# 01_MAIN.net
KiCad netlist of a schematic drawn in Altium Designer
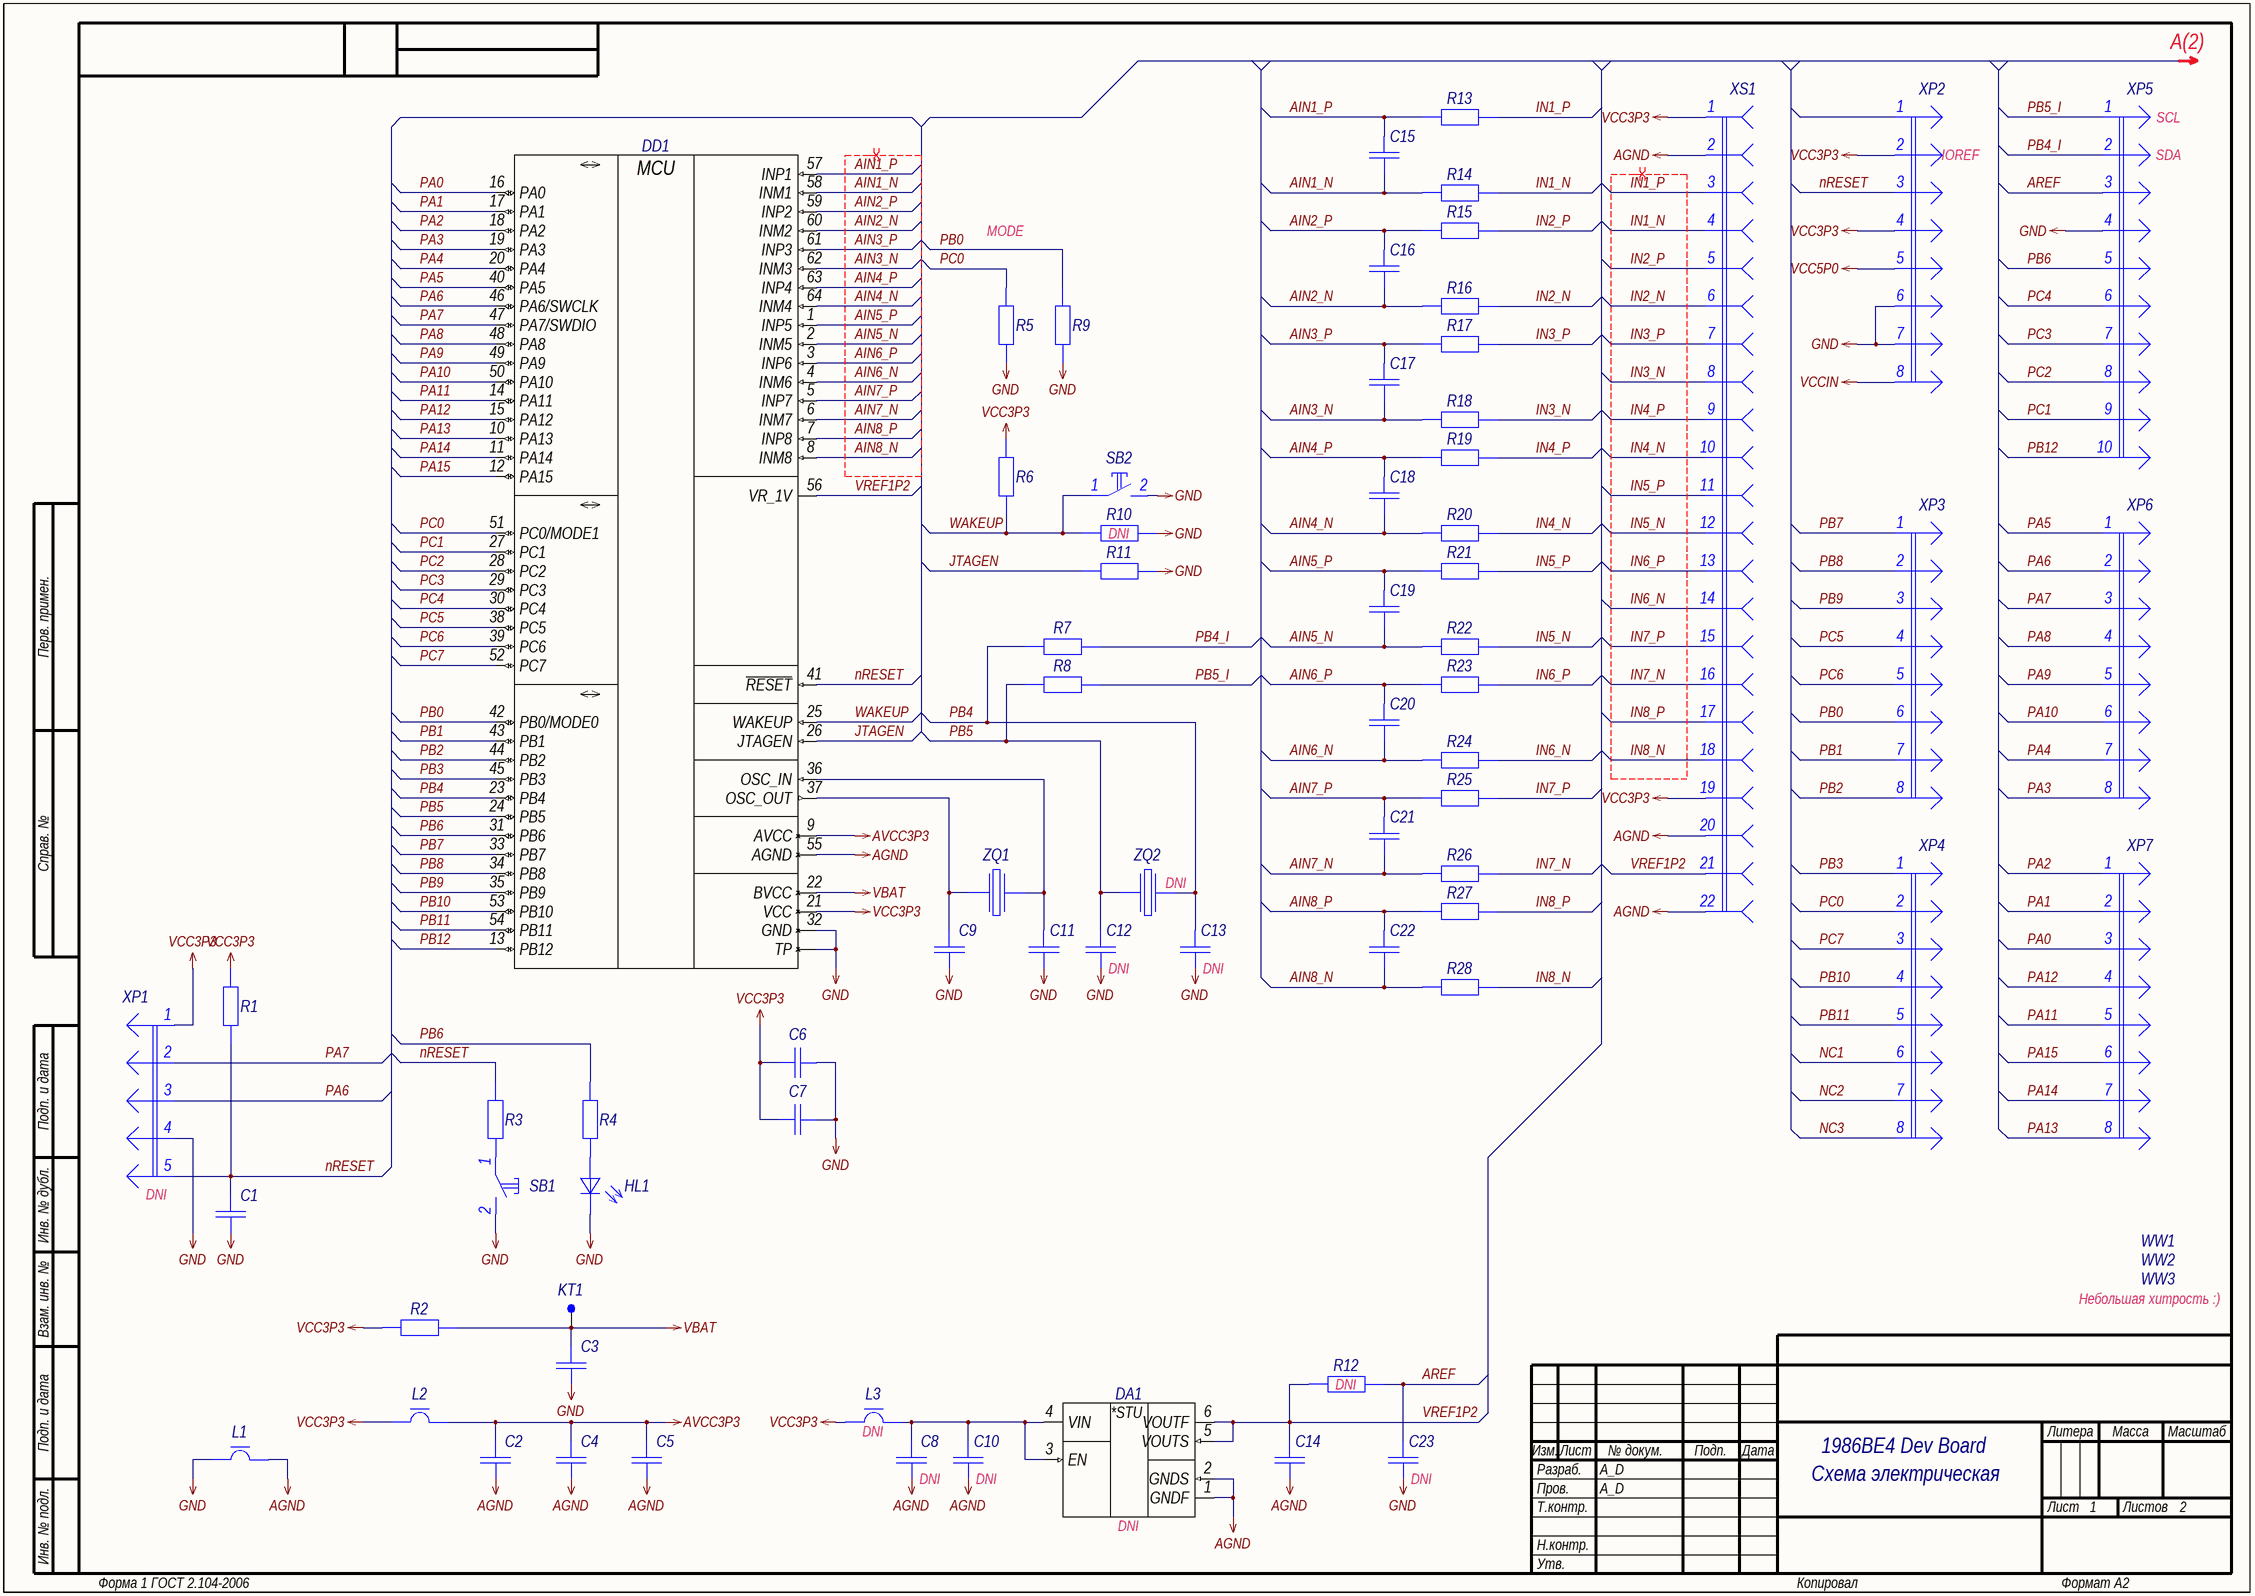
[diagram p0: 01_MAIN.SchDoc]

(export (version "E")
  (design (tool "Eeschema 10.0.6"))
  (components
    (comp (ref "C1")
      (value "Capacitor")
      (footprint "C0603_L")
      (fields
        (field (name "PART NUMBER") "GRM188R72A104KA35D")
        (field (name "VOLTAGE") "100V")
        (field (name "TOLERANCE") "±10%")
        (field (name "PUBLISHER") "Andrew Danich")
      )
      (libsource (lib "ADLib") (part "Capacitor"))
    )
    (comp (ref "C2")
      (value "Capacitor")
      (footprint "C0603_L")
      (fields
        (field (name "PART NUMBER") "GRM188R60J106ME47D")
        (field (name "VOLTAGE") "6.3V")
        (field (name "TOLERANCE") "±20%")
        (field (name "PUBLISHER") "Andrew Danich")
      )
      (libsource (lib "ADLib") (part "Capacitor"))
    )
    (comp (ref "C3")
      (value "Capacitor")
      (footprint "C0603_L")
      (fields
        (field (name "PART NUMBER") "GRM188R72A104KA35D")
        (field (name "VOLTAGE") "100V")
        (field (name "TOLERANCE") "±10%")
        (field (name "PUBLISHER") "Andrew Danich")
      )
      (libsource (lib "ADLib") (part "Capacitor"))
    )
    (comp (ref "C4")
      (value "Capacitor")
      (footprint "C0603_L")
      (fields
        (field (name "PART NUMBER") "GRM188R72A104KA35D")
        (field (name "VOLTAGE") "100V")
        (field (name "TOLERANCE") "±10%")
        (field (name "PUBLISHER") "Andrew Danich")
      )
      (libsource (lib "ADLib") (part "Capacitor"))
    )
    (comp (ref "C5")
      (value "Capacitor")
      (footprint "C0603_L")
      (fields
        (field (name "PART NUMBER") "GCJ188R72A103KA01D")
        (field (name "VOLTAGE") "100V")
        (field (name "TOLERANCE") "±10%")
        (field (name "PUBLISHER") "Andrew Danich")
      )
      (libsource (lib "ADLib") (part "Capacitor"))
    )
    (comp (ref "C6")
      (value "Capacitor")
      (footprint "C0603_L")
      (fields
        (field (name "PART NUMBER") "GRM188R72A104KA35D")
        (field (name "VOLTAGE") "100V")
        (field (name "TOLERANCE") "±10%")
        (field (name "PUBLISHER") "Andrew Danich")
      )
      (libsource (lib "ADLib") (part "Capacitor"))
    )
    (comp (ref "C7")
      (value "Capacitor")
      (footprint "C0603_L")
      (fields
        (field (name "PART NUMBER") "GCM188R71E105KA64D")
        (field (name "VOLTAGE") "25V")
        (field (name "TOLERANCE") "±10%")
        (field (name "PUBLISHER") "Andrew Danich")
      )
      (libsource (lib "ADLib") (part "Capacitor"))
    )
    (comp (ref "C8")
      (value "Capacitor")
      (footprint "C0603_L")
      (fields
        (field (name "PART NUMBER") "GCM188R71E105KA64D")
        (field (name "VOLTAGE") "25V")
        (field (name "TOLERANCE") "±10%")
        (field (name "PUBLISHER") "Andrew Danich")
      )
      (libsource (lib "ADLib") (part "Capacitor"))
    )
    (comp (ref "C9")
      (value "Capacitor")
      (footprint "C0603_L")
      (fields
        (field (name "PART NUMBER") "GCM1885C1H150JA16D")
        (field (name "VOLTAGE") "50V")
        (field (name "TOLERANCE") "±5%")
        (field (name "PUBLISHER") "Andrew Danich")
      )
      (libsource (lib "ADLib") (part "Capacitor"))
    )
    (comp (ref "C10")
      (value "Capacitor")
      (footprint "C0603_L")
      (fields
        (field (name "PART NUMBER") "GRM188R72A104KA35D")
        (field (name "VOLTAGE") "100V")
        (field (name "TOLERANCE") "±10%")
        (field (name "PUBLISHER") "Andrew Danich")
      )
      (libsource (lib "ADLib") (part "Capacitor"))
    )
    (comp (ref "C11")
      (value "Capacitor")
      (footprint "C0603_L")
      (fields
        (field (name "PART NUMBER") "GCM1885C1H150JA16D")
        (field (name "VOLTAGE") "50V")
        (field (name "TOLERANCE") "±5%")
        (field (name "PUBLISHER") "Andrew Danich")
      )
      (libsource (lib "ADLib") (part "Capacitor"))
    )
    (comp (ref "C12")
      (value "Capacitor")
      (footprint "C0603_L")
      (fields
        (field (name "PART NUMBER") "GCM1885C2A120JA16D")
        (field (name "VOLTAGE") "100V")
        (field (name "TOLERANCE") "±5%")
        (field (name "PUBLISHER") "Andrew Danich")
      )
      (libsource (lib "ADLib") (part "Capacitor"))
    )
    (comp (ref "C13")
      (value "Capacitor")
      (footprint "C0603_L")
      (fields
        (field (name "PART NUMBER") "GCM1885C2A120JA16D")
        (field (name "VOLTAGE") "100V")
        (field (name "TOLERANCE") "±5%")
        (field (name "PUBLISHER") "Andrew Danich")
      )
      (libsource (lib "ADLib") (part "Capacitor"))
    )
    (comp (ref "C14")
      (value "Capacitor")
      (footprint "C0603_L")
      (fields
        (field (name "PART NUMBER") "GRM188R72A104KA35D")
        (field (name "VOLTAGE") "100V")
        (field (name "TOLERANCE") "±10%")
        (field (name "PUBLISHER") "Andrew Danich")
      )
      (libsource (lib "ADLib") (part "Capacitor"))
    )
    (comp (ref "C15")
      (value "Capacitor")
      (footprint "C0603_L")
      (fields
        (field (name "PART NUMBER") "GCM1885C2A101JA16D")
        (field (name "VOLTAGE") "100V")
        (field (name "TOLERANCE") "±5%")
        (field (name "PUBLISHER") "Andrew Danich")
      )
      (libsource (lib "ADLib") (part "Capacitor"))
    )
    (comp (ref "C16")
      (value "Capacitor")
      (footprint "C0603_L")
      (fields
        (field (name "PART NUMBER") "GCM1885C2A101JA16D")
        (field (name "VOLTAGE") "100V")
        (field (name "TOLERANCE") "±5%")
        (field (name "PUBLISHER") "Andrew Danich")
      )
      (libsource (lib "ADLib") (part "Capacitor"))
    )
    (comp (ref "C17")
      (value "Capacitor")
      (footprint "C0603_L")
      (fields
        (field (name "PART NUMBER") "GCM1885C2A101JA16D")
        (field (name "VOLTAGE") "100V")
        (field (name "TOLERANCE") "±5%")
        (field (name "PUBLISHER") "Andrew Danich")
      )
      (libsource (lib "ADLib") (part "Capacitor"))
    )
    (comp (ref "C18")
      (value "Capacitor")
      (footprint "C0603_L")
      (fields
        (field (name "PART NUMBER") "GCM1885C2A101JA16D")
        (field (name "VOLTAGE") "100V")
        (field (name "TOLERANCE") "±5%")
        (field (name "PUBLISHER") "Andrew Danich")
      )
      (libsource (lib "ADLib") (part "Capacitor"))
    )
    (comp (ref "C19")
      (value "Capacitor")
      (footprint "C0603_L")
      (fields
        (field (name "PART NUMBER") "GCM1885C2A101JA16D")
        (field (name "VOLTAGE") "100V")
        (field (name "TOLERANCE") "±5%")
        (field (name "PUBLISHER") "Andrew Danich")
      )
      (libsource (lib "ADLib") (part "Capacitor"))
    )
    (comp (ref "C20")
      (value "Capacitor")
      (footprint "C0603_L")
      (fields
        (field (name "PART NUMBER") "GCM1885C2A101JA16D")
        (field (name "VOLTAGE") "100V")
        (field (name "TOLERANCE") "±5%")
        (field (name "PUBLISHER") "Andrew Danich")
      )
      (libsource (lib "ADLib") (part "Capacitor"))
    )
    (comp (ref "C21")
      (value "Capacitor")
      (footprint "C0603_L")
      (fields
        (field (name "PART NUMBER") "GCM1885C2A101JA16D")
        (field (name "VOLTAGE") "100V")
        (field (name "TOLERANCE") "±5%")
        (field (name "PUBLISHER") "Andrew Danich")
      )
      (libsource (lib "ADLib") (part "Capacitor"))
    )
    (comp (ref "C22")
      (value "Capacitor")
      (footprint "C0603_L")
      (fields
        (field (name "PART NUMBER") "GCM1885C2A101JA16D")
        (field (name "VOLTAGE") "100V")
        (field (name "TOLERANCE") "±5%")
        (field (name "PUBLISHER") "Andrew Danich")
      )
      (libsource (lib "ADLib") (part "Capacitor"))
    )
    (comp (ref "C23")
      (value "Capacitor")
      (footprint "C0603_L")
      (fields
        (field (name "PART NUMBER") "GRM188R72A104KA35D")
        (field (name "VOLTAGE") "100V")
        (field (name "TOLERANCE") "±10%")
        (field (name "PUBLISHER") "Andrew Danich")
      )
      (libsource (lib "ADLib") (part "Capacitor"))
    )
    (comp (ref "DA1")
      (value "ADR34xx-Series")
      (footprint "TSOT-23-6_095P290X160X100_N")
      (fields
        (field (name "PART NUMBER") "ADR3412ARJZ-R7")
        (field (name "MANUFACTURER") "Analog Devices")
        (field (name "PUBLISHER") "Andrew Danich")
      )
      (libsource (lib "ADLib") (part "ADR34xx-Series"))
    )
    (comp (ref "DD1")
      (value "1986ВЕ4У1-Series")
      (footprint "5153.64-1")
      (fields
        (field (name "PART NUMBER") "К1986ВЕ4У1К")
        (field (name "MANUFACTURER") "Миландр")
        (field (name "PUBLISHER") "Andrew Danich")
      )
      (libsource (lib "ADLib_RUS") (part "1986ВЕ4У1-Series"))
    )
    (comp (ref "HL1")
      (value "TEST")
      (footprint "LD0603_L")
      (fields (field (name "PART NUMBER") "BL-LS0603DNB") (field (name "PUBLISHER") "Andrew Danich"))
      (libsource (lib "ADLib") (part "Led-1"))
    )
    (comp (ref "KT1")
      (value "VBAT")
      (footprint "TP-SMT-C-0.8mm")
      (fields (field (name "PART NUMBER") "TestPoint-SMT") (field (name "PUBLISHER") "Andrew Danich"))
      (libsource (lib "ADLib") (part "TP-S-1"))
    )
    (comp (ref "L1")
      (value "FerriteBead")
      (footprint "L0805_L")
      (fields
        (field (name "PART NUMBER") "BLM21PG331SN1")
        (field (name "TOLERANCE") "±25%")
        (field (name "MANUFACTURER") "Murata")
        (field (name "PUBLISHER") "Andrew Danich")
      )
      (libsource (lib "ADLib") (part "FerriteBead"))
    )
    (comp (ref "L2")
      (value "FerriteBead")
      (footprint "L0603_L")
      (fields
        (field (name "PART NUMBER") "BLM18PG331SN1")
        (field (name "TOLERANCE") "±25%")
        (field (name "MANUFACTURER") "Murata")
        (field (name "PUBLISHER") "Andrew Danich")
      )
      (libsource (lib "ADLib") (part "FerriteBead"))
    )
    (comp (ref "L3")
      (value "FerriteBead")
      (footprint "L0603_L")
      (fields
        (field (name "PART NUMBER") "BLM18PG331SN1")
        (field (name "TOLERANCE") "±25%")
        (field (name "MANUFACTURER") "Murata")
        (field (name "PUBLISHER") "Andrew Danich")
      )
      (libsource (lib "ADLib") (part "FerriteBead"))
    )
    (comp (ref "R1")
      (value "Resistor")
      (footprint "R0603_L")
      (fields
        (field (name "PART NUMBER") "RC0603JR-0710KL")
        (field (name "TOLERANCE") "±5%")
        (field (name "MANUFACTURER") "Yageo")
        (field (name "PUBLISHER") "Andrew Danich")
      )
      (libsource (lib "ADLib") (part "Resistor"))
    )
    (comp (ref "R2")
      (value "Resistor")
      (footprint "R0603_L")
      (fields
        (field (name "PART NUMBER") "RC0603JR-070R")
        (field (name "TOLERANCE") "±5%")
        (field (name "MANUFACTURER") "Yageo")
        (field (name "PUBLISHER") "Andrew Danich")
      )
      (libsource (lib "ADLib") (part "Resistor"))
    )
    (comp (ref "R3")
      (value "Resistor")
      (footprint "R0603_L")
      (fields
        (field (name "PART NUMBER") "RC0603JR-07100R")
        (field (name "TOLERANCE") "±5%")
        (field (name "MANUFACTURER") "Yageo")
        (field (name "PUBLISHER") "Andrew Danich")
      )
      (libsource (lib "ADLib") (part "Resistor"))
    )
    (comp (ref "R4")
      (value "Resistor")
      (footprint "R0603_L")
      (fields
        (field (name "PART NUMBER") "RC0603JR-07330RL")
        (field (name "TOLERANCE") "±5%")
        (field (name "MANUFACTURER") "Yageo")
        (field (name "PUBLISHER") "Andrew Danich")
      )
      (libsource (lib "ADLib") (part "Resistor"))
    )
    (comp (ref "R5")
      (value "Resistor")
      (footprint "R0603_L")
      (fields
        (field (name "PART NUMBER") "RC0603JR-0710KL")
        (field (name "TOLERANCE") "±5%")
        (field (name "MANUFACTURER") "Yageo")
        (field (name "PUBLISHER") "Andrew Danich")
      )
      (libsource (lib "ADLib") (part "Resistor"))
    )
    (comp (ref "R6")
      (value "Resistor")
      (footprint "R0603_L")
      (fields
        (field (name "PART NUMBER") "RC0603JR-0710KL")
        (field (name "TOLERANCE") "±5%")
        (field (name "MANUFACTURER") "Yageo")
        (field (name "PUBLISHER") "Andrew Danich")
      )
      (libsource (lib "ADLib") (part "Resistor"))
    )
    (comp (ref "R7")
      (value "Resistor")
      (footprint "R0603_L")
      (fields
        (field (name "PART NUMBER") "RC0603JR-070R")
        (field (name "TOLERANCE") "±5%")
        (field (name "MANUFACTURER") "Yageo")
        (field (name "PUBLISHER") "Andrew Danich")
      )
      (libsource (lib "ADLib") (part "Resistor"))
    )
    (comp (ref "R8")
      (value "Resistor")
      (footprint "R0603_L")
      (fields
        (field (name "PART NUMBER") "RC0603JR-070R")
        (field (name "TOLERANCE") "±5%")
        (field (name "MANUFACTURER") "Yageo")
        (field (name "PUBLISHER") "Andrew Danich")
      )
      (libsource (lib "ADLib") (part "Resistor"))
    )
    (comp (ref "R9")
      (value "Resistor")
      (footprint "R0603_L")
      (fields
        (field (name "PART NUMBER") "RC0603JR-0710KL")
        (field (name "TOLERANCE") "±5%")
        (field (name "MANUFACTURER") "Yageo")
        (field (name "PUBLISHER") "Andrew Danich")
      )
      (libsource (lib "ADLib") (part "Resistor"))
    )
    (comp (ref "R10")
      (value "Resistor")
      (footprint "R0603_L")
      (fields
        (field (name "PART NUMBER") "RC0603JR-070R")
        (field (name "TOLERANCE") "±5%")
        (field (name "MANUFACTURER") "Yageo")
        (field (name "PUBLISHER") "Andrew Danich")
      )
      (libsource (lib "ADLib") (part "Resistor"))
    )
    (comp (ref "R11")
      (value "Resistor")
      (footprint "R0603_L")
      (fields
        (field (name "PART NUMBER") "RC0603JR-070R")
        (field (name "TOLERANCE") "±5%")
        (field (name "MANUFACTURER") "Yageo")
        (field (name "PUBLISHER") "Andrew Danich")
      )
      (libsource (lib "ADLib") (part "Resistor"))
    )
    (comp (ref "R12")
      (value "Resistor")
      (footprint "R0603_L")
      (fields
        (field (name "PART NUMBER") "RC0603JR-070R")
        (field (name "TOLERANCE") "±5%")
        (field (name "MANUFACTURER") "Yageo")
        (field (name "PUBLISHER") "Andrew Danich")
      )
      (libsource (lib "ADLib") (part "Resistor"))
    )
    (comp (ref "R13")
      (value "Resistor")
      (footprint "R0603_L")
      (fields
        (field (name "PART NUMBER") "RC0603FR-0749R9L")
        (field (name "TOLERANCE") "±1%")
        (field (name "MANUFACTURER") "Yageo")
        (field (name "PUBLISHER") "Andrew Danich")
      )
      (libsource (lib "ADLib") (part "Resistor"))
    )
    (comp (ref "R14")
      (value "Resistor")
      (footprint "R0603_L")
      (fields
        (field (name "PART NUMBER") "RC0603FR-0749R9L")
        (field (name "TOLERANCE") "±1%")
        (field (name "MANUFACTURER") "Yageo")
        (field (name "PUBLISHER") "Andrew Danich")
      )
      (libsource (lib "ADLib") (part "Resistor"))
    )
    (comp (ref "R15")
      (value "Resistor")
      (footprint "R0603_L")
      (fields
        (field (name "PART NUMBER") "RC0603FR-0749R9L")
        (field (name "TOLERANCE") "±1%")
        (field (name "MANUFACTURER") "Yageo")
        (field (name "PUBLISHER") "Andrew Danich")
      )
      (libsource (lib "ADLib") (part "Resistor"))
    )
    (comp (ref "R16")
      (value "Resistor")
      (footprint "R0603_L")
      (fields
        (field (name "PART NUMBER") "RC0603FR-0749R9L")
        (field (name "TOLERANCE") "±1%")
        (field (name "MANUFACTURER") "Yageo")
        (field (name "PUBLISHER") "Andrew Danich")
      )
      (libsource (lib "ADLib") (part "Resistor"))
    )
    (comp (ref "R17")
      (value "Resistor")
      (footprint "R0603_L")
      (fields
        (field (name "PART NUMBER") "RC0603FR-0749R9L")
        (field (name "TOLERANCE") "±1%")
        (field (name "MANUFACTURER") "Yageo")
        (field (name "PUBLISHER") "Andrew Danich")
      )
      (libsource (lib "ADLib") (part "Resistor"))
    )
    (comp (ref "R18")
      (value "Resistor")
      (footprint "R0603_L")
      (fields
        (field (name "PART NUMBER") "RC0603FR-0749R9L")
        (field (name "TOLERANCE") "±1%")
        (field (name "MANUFACTURER") "Yageo")
        (field (name "PUBLISHER") "Andrew Danich")
      )
      (libsource (lib "ADLib") (part "Resistor"))
    )
    (comp (ref "R19")
      (value "Resistor")
      (footprint "R0603_L")
      (fields
        (field (name "PART NUMBER") "RC0603FR-0749R9L")
        (field (name "TOLERANCE") "±1%")
        (field (name "MANUFACTURER") "Yageo")
        (field (name "PUBLISHER") "Andrew Danich")
      )
      (libsource (lib "ADLib") (part "Resistor"))
    )
    (comp (ref "R20")
      (value "Resistor")
      (footprint "R0603_L")
      (fields
        (field (name "PART NUMBER") "RC0603FR-0749R9L")
        (field (name "TOLERANCE") "±1%")
        (field (name "MANUFACTURER") "Yageo")
        (field (name "PUBLISHER") "Andrew Danich")
      )
      (libsource (lib "ADLib") (part "Resistor"))
    )
    (comp (ref "R21")
      (value "Resistor")
      (footprint "R0603_L")
      (fields
        (field (name "PART NUMBER") "RC0603FR-0749R9L")
        (field (name "TOLERANCE") "±1%")
        (field (name "MANUFACTURER") "Yageo")
        (field (name "PUBLISHER") "Andrew Danich")
      )
      (libsource (lib "ADLib") (part "Resistor"))
    )
    (comp (ref "R22")
      (value "Resistor")
      (footprint "R0603_L")
      (fields
        (field (name "PART NUMBER") "RC0603FR-0749R9L")
        (field (name "TOLERANCE") "±1%")
        (field (name "MANUFACTURER") "Yageo")
        (field (name "PUBLISHER") "Andrew Danich")
      )
      (libsource (lib "ADLib") (part "Resistor"))
    )
    (comp (ref "R23")
      (value "Resistor")
      (footprint "R0603_L")
      (fields
        (field (name "PART NUMBER") "RC0603FR-0749R9L")
        (field (name "TOLERANCE") "±1%")
        (field (name "MANUFACTURER") "Yageo")
        (field (name "PUBLISHER") "Andrew Danich")
      )
      (libsource (lib "ADLib") (part "Resistor"))
    )
    (comp (ref "R24")
      (value "Resistor")
      (footprint "R0603_L")
      (fields
        (field (name "PART NUMBER") "RC0603FR-0749R9L")
        (field (name "TOLERANCE") "±1%")
        (field (name "MANUFACTURER") "Yageo")
        (field (name "PUBLISHER") "Andrew Danich")
      )
      (libsource (lib "ADLib") (part "Resistor"))
    )
    (comp (ref "R25")
      (value "Resistor")
      (footprint "R0603_L")
      (fields
        (field (name "PART NUMBER") "RC0603FR-0749R9L")
        (field (name "TOLERANCE") "±1%")
        (field (name "MANUFACTURER") "Yageo")
        (field (name "PUBLISHER") "Andrew Danich")
      )
      (libsource (lib "ADLib") (part "Resistor"))
    )
    (comp (ref "R26")
      (value "Resistor")
      (footprint "R0603_L")
      (fields
        (field (name "PART NUMBER") "RC0603FR-0749R9L")
        (field (name "TOLERANCE") "±1%")
        (field (name "MANUFACTURER") "Yageo")
        (field (name "PUBLISHER") "Andrew Danich")
      )
      (libsource (lib "ADLib") (part "Resistor"))
    )
    (comp (ref "R27")
      (value "Resistor")
      (footprint "R0603_L")
      (fields
        (field (name "PART NUMBER") "RC0603FR-0749R9L")
        (field (name "TOLERANCE") "±1%")
        (field (name "MANUFACTURER") "Yageo")
        (field (name "PUBLISHER") "Andrew Danich")
      )
      (libsource (lib "ADLib") (part "Resistor"))
    )
    (comp (ref "R28")
      (value "Resistor")
      (footprint "R0603_L")
      (fields
        (field (name "PART NUMBER") "RC0603FR-0749R9L")
        (field (name "TOLERANCE") "±1%")
        (field (name "MANUFACTURER") "Yageo")
        (field (name "PUBLISHER") "Andrew Danich")
      )
      (libsource (lib "ADLib") (part "Resistor"))
    )
    (comp (ref "SB1")
      (value "СБРОС")
      (footprint "IT-1185AP")
      (fields (field (name "PART NUMBER") "IT-1185AP") (field (name "PUBLISHER") "Andrew Danich"))
      (libsource (lib "ADLib") (part "BT-01x-01p"))
    )
    (comp (ref "SB2")
      (value "WAKEUP")
      (footprint "IT-1185AP")
      (fields (field (name "PART NUMBER") "IT-1185AP") (field (name "PUBLISHER") "Andrew Danich"))
      (libsource (lib "ADLib") (part "BT-01x-01p"))
    )
    (comp (ref "WW1")
      (value "NoBody")
      (footprint "Mark-Fiducial_2.00mm")
      (fields (field (name "PART NUMBER") "MARK_FIDUCIAL") (field (name "PUBLISHER") "Andrew Danich"))
      (libsource (lib "ADLib") (part "NoBody"))
    )
    (comp (ref "WW2")
      (value "NoBody")
      (footprint "Mark-Fiducial_2.00mm")
      (fields (field (name "PART NUMBER") "MARK_FIDUCIAL") (field (name "PUBLISHER") "Andrew Danich"))
      (libsource (lib "ADLib") (part "NoBody"))
    )
    (comp (ref "WW3")
      (value "NoBody")
      (footprint "Mark-Fiducial_2.00mm")
      (fields (field (name "PART NUMBER") "MARK_FIDUCIAL") (field (name "PUBLISHER") "Andrew Danich"))
      (libsource (lib "ADLib") (part "NoBody"))
    )
    (comp (ref "XP1")
      (value "Prog")
      (footprint "PLS-5")
      (fields (field (name "PART NUMBER") "PLS-5") (field (name "PUBLISHER") "Andrew Danich"))
      (libsource (lib "ADLib") (part "Con-5-M"))
    )
    (comp (ref "XP2")
      (value "Text")
      (footprint "PLS-8")
      (fields (field (name "PART NUMBER") "PLS-8") (field (name "PUBLISHER") "Andrew Danich"))
      (libsource (lib "ADLib") (part "Con-8-M"))
    )
    (comp (ref "XP3")
      (value "Text")
      (footprint "PLS-8")
      (fields (field (name "PART NUMBER") "PLS-8") (field (name "PUBLISHER") "Andrew Danich"))
      (libsource (lib "ADLib") (part "Con-8-M"))
    )
    (comp (ref "XP4")
      (value "Text")
      (footprint "PLS-8")
      (fields (field (name "PART NUMBER") "PLS-8") (field (name "PUBLISHER") "Andrew Danich"))
      (libsource (lib "ADLib") (part "Con-8-M"))
    )
    (comp (ref "XP5")
      (value "Text")
      (footprint "PLS-10")
      (fields (field (name "PART NUMBER") "PLS-10") (field (name "PUBLISHER") "Andrew Danich"))
      (libsource (lib "ADLib") (part "Con-10-M"))
    )
    (comp (ref "XP6")
      (value "Text")
      (footprint "PLS-8")
      (fields (field (name "PART NUMBER") "PLS-8") (field (name "PUBLISHER") "Andrew Danich"))
      (libsource (lib "ADLib") (part "Con-8-M"))
    )
    (comp (ref "XP7")
      (value "Text")
      (footprint "PLS-8")
      (fields (field (name "PART NUMBER") "PLS-8") (field (name "PUBLISHER") "Andrew Danich"))
      (libsource (lib "ADLib") (part "Con-8-M"))
    )
    (comp (ref "XS1")
      (value "ADC")
      (footprint "PBD-22")
      (fields (field (name "PART NUMBER") "PBD-22") (field (name "PUBLISHER") "Andrew Danich"))
      (libsource (lib "ADLib") (part "Con-22-F"))
    )
    (comp (ref "ZQ1")
      (value "Crystal")
      (footprint "SMD 5x3.2mm")
      (fields
        (field (name "PART NUMBER") "KX-9A 8.0 MHz 30/50/100 16 pF")
        (field (name "MANUFACTURER") "Geyer")
        (field (name "PUBLISHER") "Andrew Danich")
      )
      (libsource (lib "ADLib") (part "Crystal"))
    )
    (comp (ref "ZQ2")
      (value "Crystal-1_4p")
      (footprint "DSO-N4")
      (fields
        (field (name "PART NUMBER") "MC306-32.768KHz")
        (field (name "MANUFACTURER") "Seiko Epson Corporation")
        (field (name "PUBLISHER") "Andrew Danich")
      )
      (libsource (lib "ADLib") (part "Crystal-1_4p"))
    )
  )
  (nets
    (net (code "1") (name "/AIN1_N") (class "Default")
      (node (ref "C15") (pin "1") (pinfunction "1_1") (pintype "passive"))
      (node (ref "DD1") (pin "58") (pinfunction "INM1_58") (pintype "input"))
      (node (ref "R14") (pin "1") (pinfunction "1_1") (pintype "passive"))
    )
    (net (code "2") (name "/AIN1_P") (class "Default")
      (node (ref "C15") (pin "2") (pinfunction "2_2") (pintype "passive"))
      (node (ref "DD1") (pin "57") (pinfunction "INP1_57") (pintype "input"))
      (node (ref "R13") (pin "1") (pinfunction "1_1") (pintype "passive"))
    )
    (net (code "3") (name "/AIN2_N") (class "Default")
      (node (ref "C16") (pin "1") (pinfunction "1_1") (pintype "passive"))
      (node (ref "DD1") (pin "60") (pinfunction "INM2_60") (pintype "input"))
      (node (ref "R16") (pin "1") (pinfunction "1_1") (pintype "passive"))
    )
    (net (code "4") (name "/AIN2_P") (class "Default")
      (node (ref "C16") (pin "2") (pinfunction "2_2") (pintype "passive"))
      (node (ref "DD1") (pin "59") (pinfunction "INP2_59") (pintype "input"))
      (node (ref "R15") (pin "1") (pinfunction "1_1") (pintype "passive"))
    )
    (net (code "5") (name "/AIN3_N") (class "Default")
      (node (ref "C17") (pin "1") (pinfunction "1_1") (pintype "passive"))
      (node (ref "DD1") (pin "62") (pinfunction "INM3_62") (pintype "input"))
      (node (ref "R18") (pin "1") (pinfunction "1_1") (pintype "passive"))
    )
    (net (code "6") (name "/AIN3_P") (class "Default")
      (node (ref "C17") (pin "2") (pinfunction "2_2") (pintype "passive"))
      (node (ref "DD1") (pin "61") (pinfunction "INP3_61") (pintype "input"))
      (node (ref "R17") (pin "1") (pinfunction "1_1") (pintype "passive"))
    )
    (net (code "7") (name "/AIN4_N") (class "Default")
      (node (ref "C18") (pin "1") (pinfunction "1_1") (pintype "passive"))
      (node (ref "DD1") (pin "64") (pinfunction "INM4_64") (pintype "input"))
      (node (ref "R20") (pin "1") (pinfunction "1_1") (pintype "passive"))
    )
    (net (code "8") (name "/AIN4_P") (class "Default")
      (node (ref "C18") (pin "2") (pinfunction "2_2") (pintype "passive"))
      (node (ref "DD1") (pin "63") (pinfunction "INP4_63") (pintype "input"))
      (node (ref "R19") (pin "1") (pinfunction "1_1") (pintype "passive"))
    )
    (net (code "9") (name "/AIN5_N") (class "Default")
      (node (ref "C19") (pin "1") (pinfunction "1_1") (pintype "passive"))
      (node (ref "DD1") (pin "2") (pinfunction "INM5_2") (pintype "input"))
      (node (ref "R22") (pin "1") (pinfunction "1_1") (pintype "passive"))
    )
    (net (code "10") (name "/AIN5_P") (class "Default")
      (node (ref "C19") (pin "2") (pinfunction "2_2") (pintype "passive"))
      (node (ref "DD1") (pin "1") (pinfunction "INP5_1") (pintype "input"))
      (node (ref "R21") (pin "1") (pinfunction "1_1") (pintype "passive"))
    )
    (net (code "11") (name "/AIN6_N") (class "Default")
      (node (ref "C20") (pin "1") (pinfunction "1_1") (pintype "passive"))
      (node (ref "DD1") (pin "4") (pinfunction "INM6_4") (pintype "input"))
      (node (ref "R24") (pin "1") (pinfunction "1_1") (pintype "passive"))
    )
    (net (code "12") (name "/AIN6_P") (class "Default")
      (node (ref "C20") (pin "2") (pinfunction "2_2") (pintype "passive"))
      (node (ref "DD1") (pin "3") (pinfunction "INP6_3") (pintype "input"))
      (node (ref "R23") (pin "1") (pinfunction "1_1") (pintype "passive"))
    )
    (net (code "13") (name "/AIN7_N") (class "Default")
      (node (ref "C21") (pin "1") (pinfunction "1_1") (pintype "passive"))
      (node (ref "DD1") (pin "6") (pinfunction "INM7_6") (pintype "input"))
      (node (ref "R26") (pin "1") (pinfunction "1_1") (pintype "passive"))
    )
    (net (code "14") (name "/AIN7_P") (class "Default")
      (node (ref "C21") (pin "2") (pinfunction "2_2") (pintype "passive"))
      (node (ref "DD1") (pin "5") (pinfunction "INP7_5") (pintype "input"))
      (node (ref "R25") (pin "1") (pinfunction "1_1") (pintype "passive"))
    )
    (net (code "15") (name "/AIN8_N") (class "Default")
      (node (ref "C22") (pin "1") (pinfunction "1_1") (pintype "passive"))
      (node (ref "DD1") (pin "8") (pinfunction "INM8_8") (pintype "input"))
      (node (ref "R28") (pin "1") (pinfunction "1_1") (pintype "passive"))
    )
    (net (code "16") (name "/AIN8_P") (class "Default")
      (node (ref "C22") (pin "2") (pinfunction "2_2") (pintype "passive"))
      (node (ref "DD1") (pin "7") (pinfunction "INP8_7") (pintype "input"))
      (node (ref "R27") (pin "1") (pinfunction "1_1") (pintype "passive"))
    )
    (net (code "17") (name "/AREF") (class "Default")
      (node (ref "C23") (pin "2") (pinfunction "2_2") (pintype "passive"))
      (node (ref "R12") (pin "2") (pinfunction "2_2") (pintype "passive"))
      (node (ref "XP5") (pin "3") (pintype "passive"))
    )
    (net (code "18") (name "/IN1_N") (class "Default")
      (node (ref "R14") (pin "2") (pinfunction "2_2") (pintype "passive"))
      (node (ref "XS1") (pin "4") (pintype "passive"))
    )
    (net (code "19") (name "/IN1_P") (class "Default")
      (node (ref "R13") (pin "2") (pinfunction "2_2") (pintype "passive"))
      (node (ref "XS1") (pin "3") (pintype "passive"))
    )
    (net (code "20") (name "/IN2_N") (class "Default")
      (node (ref "R16") (pin "2") (pinfunction "2_2") (pintype "passive"))
      (node (ref "XS1") (pin "6") (pintype "passive"))
    )
    (net (code "21") (name "/IN2_P") (class "Default")
      (node (ref "R15") (pin "2") (pinfunction "2_2") (pintype "passive"))
      (node (ref "XS1") (pin "5") (pintype "passive"))
    )
    (net (code "22") (name "/IN3_N") (class "Default")
      (node (ref "R18") (pin "2") (pinfunction "2_2") (pintype "passive"))
      (node (ref "XS1") (pin "8") (pintype "passive"))
    )
    (net (code "23") (name "/IN3_P") (class "Default")
      (node (ref "R17") (pin "2") (pinfunction "2_2") (pintype "passive"))
      (node (ref "XS1") (pin "7") (pintype "passive"))
    )
    (net (code "24") (name "/IN4_N") (class "Default")
      (node (ref "R20") (pin "2") (pinfunction "2_2") (pintype "passive"))
      (node (ref "XS1") (pin "10") (pintype "passive"))
    )
    (net (code "25") (name "/IN4_P") (class "Default")
      (node (ref "R19") (pin "2") (pinfunction "2_2") (pintype "passive"))
      (node (ref "XS1") (pin "9") (pintype "passive"))
    )
    (net (code "26") (name "/IN5_N") (class "Default")
      (node (ref "R22") (pin "2") (pinfunction "2_2") (pintype "passive"))
      (node (ref "XS1") (pin "12") (pintype "passive"))
    )
    (net (code "27") (name "/IN5_P") (class "Default")
      (node (ref "R21") (pin "2") (pinfunction "2_2") (pintype "passive"))
      (node (ref "XS1") (pin "11") (pintype "passive"))
    )
    (net (code "28") (name "/IN6_N") (class "Default")
      (node (ref "R24") (pin "2") (pinfunction "2_2") (pintype "passive"))
      (node (ref "XS1") (pin "14") (pintype "passive"))
    )
    (net (code "29") (name "/IN6_P") (class "Default")
      (node (ref "R23") (pin "2") (pinfunction "2_2") (pintype "passive"))
      (node (ref "XS1") (pin "13") (pintype "passive"))
    )
    (net (code "30") (name "/IN7_N") (class "Default")
      (node (ref "R26") (pin "2") (pinfunction "2_2") (pintype "passive"))
      (node (ref "XS1") (pin "16") (pintype "passive"))
    )
    (net (code "31") (name "/IN7_P") (class "Default")
      (node (ref "R25") (pin "2") (pinfunction "2_2") (pintype "passive"))
      (node (ref "XS1") (pin "15") (pintype "passive"))
    )
    (net (code "32") (name "/IN8_N") (class "Default")
      (node (ref "R28") (pin "2") (pinfunction "2_2") (pintype "passive"))
      (node (ref "XS1") (pin "18") (pintype "passive"))
    )
    (net (code "33") (name "/IN8_P") (class "Default")
      (node (ref "R27") (pin "2") (pinfunction "2_2") (pintype "passive"))
      (node (ref "XS1") (pin "17") (pintype "passive"))
    )
    (net (code "34") (name "/JTAGEN") (class "Default")
      (node (ref "DD1") (pin "26") (pinfunction "JTAGEN_26") (pintype "input"))
      (node (ref "R11") (pin "1") (pinfunction "1_1") (pintype "passive"))
    )
    (net (code "35") (name "/NC1") (class "Default") (node (ref "XP4") (pin "6") (pintype "passive")))
    (net (code "36") (name "/NC2") (class "Default") (node (ref "XP4") (pin "7") (pintype "passive")))
    (net (code "37") (name "/NC3") (class "Default") (node (ref "XP4") (pin "8") (pintype "passive")))
    (net (code "38") (name "/PA0") (class "Default")
      (node (ref "DD1") (pin "16") (pinfunction "PA0_16") (pintype "bidirectional"))
      (node (ref "XP7") (pin "3") (pintype "passive"))
    )
    (net (code "39") (name "/PA1") (class "Default")
      (node (ref "DD1") (pin "17") (pinfunction "PA1_17") (pintype "bidirectional"))
      (node (ref "XP7") (pin "2") (pintype "passive"))
    )
    (net (code "40") (name "/PA2") (class "Default")
      (node (ref "DD1") (pin "18") (pinfunction "PA2_18") (pintype "bidirectional"))
      (node (ref "XP7") (pin "1") (pintype "passive"))
    )
    (net (code "41") (name "/PA3") (class "Default")
      (node (ref "DD1") (pin "19") (pinfunction "PA3_19") (pintype "bidirectional"))
      (node (ref "XP6") (pin "8") (pintype "passive"))
    )
    (net (code "42") (name "/PA4") (class "Default")
      (node (ref "DD1") (pin "20") (pinfunction "PA4_20") (pintype "bidirectional"))
      (node (ref "XP6") (pin "7") (pintype "passive"))
    )
    (net (code "43") (name "/PA5") (class "Default")
      (node (ref "DD1") (pin "40") (pinfunction "PA5_40") (pintype "bidirectional"))
      (node (ref "XP6") (pin "1") (pintype "passive"))
    )
    (net (code "44") (name "/PA6") (class "Default")
      (node (ref "DD1") (pin "46") (pinfunction "PA6/SWCLK_46") (pintype "bidirectional"))
      (node (ref "XP1") (pin "3") (pintype "passive"))
      (node (ref "XP6") (pin "2") (pintype "passive"))
    )
    (net (code "45") (name "/PA7") (class "Default")
      (node (ref "DD1") (pin "47") (pinfunction "PA7/SWDIO_47") (pintype "bidirectional"))
      (node (ref "XP1") (pin "2") (pintype "passive"))
      (node (ref "XP6") (pin "3") (pintype "passive"))
    )
    (net (code "46") (name "/PA8") (class "Default")
      (node (ref "DD1") (pin "48") (pinfunction "PA8_48") (pintype "bidirectional"))
      (node (ref "XP6") (pin "4") (pintype "passive"))
    )
    (net (code "47") (name "/PA9") (class "Default")
      (node (ref "DD1") (pin "49") (pinfunction "PA9_49") (pintype "bidirectional"))
      (node (ref "XP6") (pin "5") (pintype "passive"))
    )
    (net (code "48") (name "/PA10") (class "Default")
      (node (ref "DD1") (pin "50") (pinfunction "PA10_50") (pintype "bidirectional"))
      (node (ref "XP6") (pin "6") (pintype "passive"))
    )
    (net (code "49") (name "/PA11") (class "Default")
      (node (ref "DD1") (pin "14") (pinfunction "PA11_14") (pintype "bidirectional"))
      (node (ref "XP7") (pin "5") (pintype "passive"))
    )
    (net (code "50") (name "/PA12") (class "Default")
      (node (ref "DD1") (pin "15") (pinfunction "PA12_15") (pintype "bidirectional"))
      (node (ref "XP7") (pin "4") (pintype "passive"))
    )
    (net (code "51") (name "/PA13") (class "Default")
      (node (ref "DD1") (pin "10") (pinfunction "PA13_10") (pintype "bidirectional"))
      (node (ref "XP7") (pin "8") (pintype "passive"))
    )
    (net (code "52") (name "/PA14") (class "Default")
      (node (ref "DD1") (pin "11") (pinfunction "PA14_11") (pintype "bidirectional"))
      (node (ref "XP7") (pin "7") (pintype "passive"))
    )
    (net (code "53") (name "/PA15") (class "Default")
      (node (ref "DD1") (pin "12") (pinfunction "PA15_12") (pintype "bidirectional"))
      (node (ref "XP7") (pin "6") (pintype "passive"))
    )
    (net (code "54") (name "/PB0") (class "Default")
      (node (ref "DD1") (pin "42") (pinfunction "PB0/MODE0_42") (pintype "bidirectional"))
      (node (ref "R9") (pin "2") (pinfunction "2_2") (pintype "passive"))
      (node (ref "XP3") (pin "6") (pintype "passive"))
    )
    (net (code "55") (name "/PB1") (class "Default")
      (node (ref "DD1") (pin "43") (pinfunction "PB1_43") (pintype "bidirectional"))
      (node (ref "XP3") (pin "7") (pintype "passive"))
    )
    (net (code "56") (name "/PB2") (class "Default")
      (node (ref "DD1") (pin "44") (pinfunction "PB2_44") (pintype "bidirectional"))
      (node (ref "XP3") (pin "8") (pintype "passive"))
    )
    (net (code "57") (name "/PB3") (class "Default")
      (node (ref "DD1") (pin "45") (pinfunction "PB3_45") (pintype "bidirectional"))
      (node (ref "XP4") (pin "1") (pintype "passive"))
    )
    (net (code "58") (name "/PB4") (class "Default")
      (node (ref "C13") (pin "2") (pinfunction "2_2") (pintype "passive"))
      (node (ref "DD1") (pin "23") (pinfunction "PB4_23") (pintype "bidirectional"))
      (node (ref "R7") (pin "1") (pinfunction "1_1") (pintype "passive"))
      (node (ref "ZQ2") (pin "1") (pinfunction "1_1") (pintype "passive"))
    )
    (net (code "59") (name "/PB4_I") (class "Default")
      (node (ref "R7") (pin "2") (pinfunction "2_2") (pintype "passive"))
      (node (ref "XP5") (pin "2") (pintype "passive"))
    )
    (net (code "60") (name "/PB5") (class "Default")
      (node (ref "C12") (pin "2") (pinfunction "2_2") (pintype "passive"))
      (node (ref "DD1") (pin "24") (pinfunction "PB5_24") (pintype "bidirectional"))
      (node (ref "R8") (pin "1") (pinfunction "1_1") (pintype "passive"))
      (node (ref "ZQ2") (pin "4") (pinfunction "4_4") (pintype "passive"))
    )
    (net (code "61") (name "/PB5_I") (class "Default")
      (node (ref "R8") (pin "2") (pinfunction "2_2") (pintype "passive"))
      (node (ref "XP5") (pin "1") (pintype "passive"))
    )
    (net (code "62") (name "/PB6") (class "Default")
      (node (ref "DD1") (pin "31") (pinfunction "PB6_31") (pintype "bidirectional"))
      (node (ref "R4") (pin "2") (pinfunction "2_2") (pintype "passive"))
      (node (ref "XP5") (pin "5") (pintype "passive"))
    )
    (net (code "63") (name "/PB7") (class "Default")
      (node (ref "DD1") (pin "33") (pinfunction "PB7_33") (pintype "bidirectional"))
      (node (ref "XP3") (pin "1") (pintype "passive"))
    )
    (net (code "64") (name "/PB8") (class "Default")
      (node (ref "DD1") (pin "34") (pinfunction "PB8_34") (pintype "bidirectional"))
      (node (ref "XP3") (pin "2") (pintype "passive"))
    )
    (net (code "65") (name "/PB9") (class "Default")
      (node (ref "DD1") (pin "35") (pinfunction "PB9_35") (pintype "bidirectional"))
      (node (ref "XP3") (pin "3") (pintype "passive"))
    )
    (net (code "66") (name "/PB10") (class "Default")
      (node (ref "DD1") (pin "53") (pinfunction "PB10_53") (pintype "bidirectional"))
      (node (ref "XP4") (pin "4") (pintype "passive"))
    )
    (net (code "67") (name "/PB11") (class "Default")
      (node (ref "DD1") (pin "54") (pinfunction "PB11_54") (pintype "bidirectional"))
      (node (ref "XP4") (pin "5") (pintype "passive"))
    )
    (net (code "68") (name "/PB12") (class "Default")
      (node (ref "DD1") (pin "13") (pinfunction "PB12_13") (pintype "bidirectional"))
      (node (ref "XP5") (pin "10") (pintype "passive"))
    )
    (net (code "69") (name "/PC0") (class "Default")
      (node (ref "DD1") (pin "51") (pinfunction "PC0/MODE1_51") (pintype "bidirectional"))
      (node (ref "R5") (pin "2") (pinfunction "2_2") (pintype "passive"))
      (node (ref "XP4") (pin "2") (pintype "passive"))
    )
    (net (code "70") (name "/PC1") (class "Default")
      (node (ref "DD1") (pin "27") (pinfunction "PC1_27") (pintype "bidirectional"))
      (node (ref "XP5") (pin "9") (pintype "passive"))
    )
    (net (code "71") (name "/PC2") (class "Default")
      (node (ref "DD1") (pin "28") (pinfunction "PC2_28") (pintype "bidirectional"))
      (node (ref "XP5") (pin "8") (pintype "passive"))
    )
    (net (code "72") (name "/PC3") (class "Default")
      (node (ref "DD1") (pin "29") (pinfunction "PC3_29") (pintype "bidirectional"))
      (node (ref "XP5") (pin "7") (pintype "passive"))
    )
    (net (code "73") (name "/PC4") (class "Default")
      (node (ref "DD1") (pin "30") (pinfunction "PC4_30") (pintype "bidirectional"))
      (node (ref "XP5") (pin "6") (pintype "passive"))
    )
    (net (code "74") (name "/PC5") (class "Default")
      (node (ref "DD1") (pin "38") (pinfunction "PC5_38") (pintype "bidirectional"))
      (node (ref "XP3") (pin "4") (pintype "passive"))
    )
    (net (code "75") (name "/PC6") (class "Default")
      (node (ref "DD1") (pin "39") (pinfunction "PC6_39") (pintype "bidirectional"))
      (node (ref "XP3") (pin "5") (pintype "passive"))
    )
    (net (code "76") (name "/PC7") (class "Default")
      (node (ref "DD1") (pin "52") (pinfunction "PC7_52") (pintype "bidirectional"))
      (node (ref "XP4") (pin "3") (pintype "passive"))
    )
    (net (code "77") (name "/VREF1P2") (class "Default")
      (node (ref "C14") (pin "2") (pinfunction "2_2") (pintype "passive"))
      (node (ref "DA1") (pin "5") (pinfunction "VOUTS_5") (pintype "input"))
      (node (ref "DA1") (pin "6") (pinfunction "VOUTF_6") (pintype "power_in"))
      (node (ref "DD1") (pin "56") (pinfunction "VR_1V_56") (pintype "power_in"))
      (node (ref "R12") (pin "1") (pinfunction "1_1") (pintype "passive"))
      (node (ref "XS1") (pin "21") (pintype "passive"))
    )
    (net (code "78") (name "/WAKEUP") (class "Default")
      (node (ref "DD1") (pin "25") (pinfunction "WAKEUP_25") (pintype "input"))
      (node (ref "R10") (pin "1") (pinfunction "1_1") (pintype "passive"))
      (node (ref "R6") (pin "1") (pinfunction "1_1") (pintype "passive"))
      (node (ref "SB2") (pin "1") (pintype "passive"))
    )
    (net (code "79") (name "/nRESET") (class "Default")
      (node (ref "C1") (pin "2") (pinfunction "2_2") (pintype "passive"))
      (node (ref "DD1") (pin "41") (pinfunction "~{RESET}_41") (pintype "input"))
      (node (ref "R1") (pin "1") (pinfunction "1_1") (pintype "passive"))
      (node (ref "R3") (pin "2") (pinfunction "2_2") (pintype "passive"))
      (node (ref "XP1") (pin "5") (pintype "passive"))
      (node (ref "XP2") (pin "3") (pintype "passive"))
    )
    (net (code "80") (name "AGND") (class "Default")
      (node (ref "C10") (pin "1") (pinfunction "1_1") (pintype "passive"))
      (node (ref "C14") (pin "1") (pinfunction "1_1") (pintype "passive"))
      (node (ref "C2") (pin "1") (pinfunction "1_1") (pintype "passive"))
      (node (ref "C4") (pin "1") (pinfunction "1_1") (pintype "passive"))
      (node (ref "C5") (pin "1") (pinfunction "1_1") (pintype "passive"))
      (node (ref "C8") (pin "1") (pinfunction "1_1") (pintype "passive"))
      (node (ref "DA1") (pin "1") (pinfunction "GNDF_1") (pintype "power_in"))
      (node (ref "DA1") (pin "2") (pinfunction "GNDS_2") (pintype "input"))
      (node (ref "DD1") (pin "55") (pinfunction "AGND_55") (pintype "power_in"))
      (node (ref "L1") (pin "2") (pinfunction "2_2") (pintype "passive"))
      (node (ref "XS1") (pin "2") (pintype "passive"))
      (node (ref "XS1") (pin "20") (pintype "passive"))
      (node (ref "XS1") (pin "22") (pintype "passive"))
    )
    (net (code "81") (name "AVCC3P3") (class "Default")
      (node (ref "C2") (pin "2") (pinfunction "2_2") (pintype "passive"))
      (node (ref "C4") (pin "2") (pinfunction "2_2") (pintype "passive"))
      (node (ref "C5") (pin "2") (pinfunction "2_2") (pintype "passive"))
      (node (ref "DD1") (pin "9") (pinfunction "AVCC_9") (pintype "power_in"))
      (node (ref "L2") (pin "2") (pinfunction "2_2") (pintype "passive"))
    )
    (net (code "82") (name "GND") (class "Default")
      (node (ref "C1") (pin "1") (pinfunction "1_1") (pintype "passive"))
      (node (ref "C11") (pin "1") (pinfunction "1_1") (pintype "passive"))
      (node (ref "C12") (pin "1") (pinfunction "1_1") (pintype "passive"))
      (node (ref "C13") (pin "1") (pinfunction "1_1") (pintype "passive"))
      (node (ref "C23") (pin "1") (pinfunction "1_1") (pintype "passive"))
      (node (ref "C3") (pin "1") (pinfunction "1_1") (pintype "passive"))
      (node (ref "C6") (pin "1") (pinfunction "1_1") (pintype "passive"))
      (node (ref "C7") (pin "1") (pinfunction "1_1") (pintype "passive"))
      (node (ref "C9") (pin "1") (pinfunction "1_1") (pintype "passive"))
      (node (ref "DD1") (pin "32") (pinfunction "GND_32") (pintype "power_in"))
      (node (ref "DD1") (pin "TP") (pinfunction "TP_TP") (pintype "power_in"))
      (node (ref "HL1") (pin "2") (pinfunction "К_2") (pintype "passive"))
      (node (ref "L1") (pin "1") (pinfunction "1_1") (pintype "passive"))
      (node (ref "R10") (pin "2") (pinfunction "2_2") (pintype "passive"))
      (node (ref "R11") (pin "2") (pinfunction "2_2") (pintype "passive"))
      (node (ref "R5") (pin "1") (pinfunction "1_1") (pintype "passive"))
      (node (ref "R9") (pin "1") (pinfunction "1_1") (pintype "passive"))
      (node (ref "SB1") (pin "2") (pintype "passive"))
      (node (ref "SB2") (pin "2") (pintype "passive"))
      (node (ref "XP1") (pin "4") (pintype "passive"))
      (node (ref "XP2") (pin "6") (pintype "passive"))
      (node (ref "XP2") (pin "7") (pintype "passive"))
      (node (ref "XP5") (pin "4") (pintype "passive"))
    )
    (net (code "83") (name "Net-(DA1-EN)") (class "Default")
      (node (ref "C10") (pin "2") (pinfunction "2_2") (pintype "passive"))
      (node (ref "C8") (pin "2") (pinfunction "2_2") (pintype "passive"))
      (node (ref "DA1") (pin "3") (pinfunction "EN_3") (pintype "input"))
      (node (ref "DA1") (pin "4") (pinfunction "VIN_4") (pintype "power_in"))
      (node (ref "L3") (pin "2") (pinfunction "2_2") (pintype "passive"))
    )
    (net (code "84") (name "Net-(DD1-OSC_IN)") (class "Default")
      (node (ref "C11") (pin "2") (pinfunction "2_2") (pintype "passive"))
      (node (ref "DD1") (pin "36") (pinfunction "OSC_IN_36") (pintype "input"))
      (node (ref "ZQ1") (pin "3") (pinfunction "3_3") (pintype "passive"))
    )
    (net (code "85") (name "Net-(DD1-OSC_OUT)") (class "Default")
      (node (ref "C9") (pin "2") (pinfunction "2_2") (pintype "passive"))
      (node (ref "DD1") (pin "37") (pinfunction "OSC_OUT_37") (pintype "output"))
      (node (ref "ZQ1") (pin "1") (pinfunction "1_1") (pintype "passive"))
    )
    (net (code "86") (name "Net-(HL1-А)") (class "Default")
      (node (ref "HL1") (pin "1") (pinfunction "А_1") (pintype "passive"))
      (node (ref "R4") (pin "1") (pinfunction "1_1") (pintype "passive"))
    )
    (net (code "87") (name "Net-(R3-Pad1)") (class "Default")
      (node (ref "R3") (pin "1") (pinfunction "1_1") (pintype "passive"))
      (node (ref "SB1") (pin "1") (pintype "passive"))
    )
    (net (code "88") (name "VBAT") (class "Default")
      (node (ref "C3") (pin "2") (pinfunction "2_2") (pintype "passive"))
      (node (ref "DD1") (pin "22") (pinfunction "BVCC_22") (pintype "power_in"))
      (node (ref "KT1") (pin "1") (pinfunction "1_1") (pintype "passive"))
      (node (ref "R2") (pin "2") (pinfunction "2_2") (pintype "passive"))
    )
    (net (code "89") (name "VCC3P3") (class "Default")
      (node (ref "C6") (pin "2") (pinfunction "2_2") (pintype "passive"))
      (node (ref "C7") (pin "2") (pinfunction "2_2") (pintype "passive"))
      (node (ref "DD1") (pin "21") (pinfunction "VCC_21") (pintype "power_in"))
      (node (ref "L2") (pin "1") (pinfunction "1_1") (pintype "passive"))
      (node (ref "L3") (pin "1") (pinfunction "1_1") (pintype "passive"))
      (node (ref "R1") (pin "2") (pinfunction "2_2") (pintype "passive"))
      (node (ref "R2") (pin "1") (pinfunction "1_1") (pintype "passive"))
      (node (ref "R6") (pin "2") (pinfunction "2_2") (pintype "passive"))
      (node (ref "XP1") (pin "1") (pintype "passive"))
      (node (ref "XP2") (pin "2") (pintype "passive"))
      (node (ref "XP2") (pin "4") (pintype "passive"))
      (node (ref "XS1") (pin "1") (pintype "passive"))
      (node (ref "XS1") (pin "19") (pintype "passive"))
    )
    (net (code "90") (name "VCC5P0") (class "Default") (node (ref "XP2") (pin "5") (pintype "passive")))
    (net (code "91") (name "VCCIN") (class "Default") (node (ref "XP2") (pin "8") (pintype "passive")))
    (net (code "92") (name "unconnected-(XP2-Pad1)") (class "Default")
      (node (ref "XP2") (pin "1") (pintype "passive"))
    )
  )
)
